# pwr.net
KiCad netlist of a schematic drawn in Altium Designer
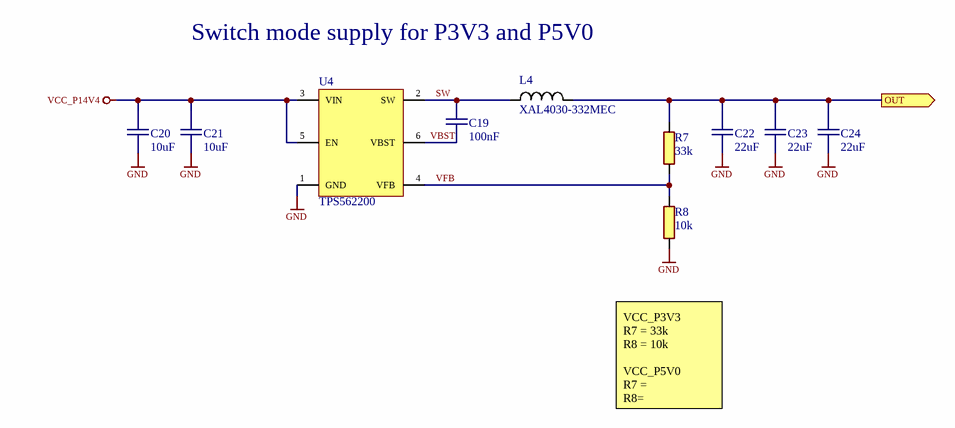
[diagram p0: pwr.SchDoc]

(export (version "E")
  (design (tool "Eeschema 10.0.6"))
  (components
    (comp (ref "C19")
      (value "100nF")
      (footprint "CAPC0603(1608)55_N")
      (description "X7R 50V 5%")
      (libsource (lib "OVLib_64") (part "CAP"))
    )
    (comp (ref "C20")
      (value "10uF")
      (footprint "CAPC1206(3216)170_N")
      (description "X5R 50V 10%")
      (libsource (lib "OVLib_64") (part "CAP"))
    )
    (comp (ref "C21")
      (value "10uF")
      (footprint "CAPC1206(3216)170_N")
      (description "X5R 50V 10%")
      (libsource (lib "OVLib_64") (part "CAP"))
    )
    (comp (ref "C22")
      (value "22uF")
      (footprint "CAPC1206(3216)170_N")
      (description "10V 10% Tantalum")
      (libsource (lib "OVLib_64") (part "CAP"))
    )
    (comp (ref "C23")
      (value "22uF")
      (footprint "CAPC1206(3216)170_N")
      (description "10V 10% Tantalum")
      (libsource (lib "OVLib_64") (part "CAP"))
    )
    (comp (ref "C24")
      (value "22uF")
      (footprint "CAPC1206(3216)170_N")
      (description "10V 10% Tantalum")
      (libsource (lib "OVLib_64") (part "CAP"))
    )
    (comp (ref "L4")
      (value "XAL4030-332MEC")
      (footprint "XAL4030")
      (description "3.3µH")
      (libsource (lib "OVLib_64") (part "IND_GENERIC"))
    )
    (comp (ref "R7")
      (value "33k")
      (footprint "RESC0603(1608)_N")
      (description "0.1W 1% Thick film resistor")
      (libsource (lib "OVLib_64") (part "Resistor2"))
    )
    (comp (ref "R8")
      (value "10k")
      (footprint "RESC0603(1608)_N")
      (description "0.1W 1% Thick film resistor")
      (libsource (lib "OVLib_64") (part "Resistor2"))
    )
    (comp (ref "U4")
      (value "TPS562200")
      (footprint "SOT95P280X145-6N")
      (libsource (lib "OVLib_64") (part "TPS562200"))
    )
  )
  (nets
    (net (code "1") (name "/OUT") (class "Default")
      (node (ref "C22") (pin "2") (pinfunction "2_2") (pintype "passive"))
      (node (ref "C23") (pin "2") (pinfunction "2_2") (pintype "passive"))
      (node (ref "C24") (pin "2") (pinfunction "2_2") (pintype "passive"))
      (node (ref "L4") (pin "2") (pinfunction "2_2") (pintype "passive"))
      (node (ref "R7") (pin "2") (pinfunction "2_2") (pintype "passive"))
    )
    (net (code "2") (name "/SW") (class "Default")
      (node (ref "C19") (pin "2") (pinfunction "2_2") (pintype "passive"))
      (node (ref "L4") (pin "1") (pinfunction "1_1") (pintype "passive"))
      (node (ref "U4") (pin "2") (pinfunction "SW_2") (pintype "passive"))
    )
    (net (code "3") (name "/VBST") (class "Default")
      (node (ref "C19") (pin "1") (pinfunction "1_1") (pintype "passive"))
      (node (ref "U4") (pin "6") (pinfunction "VBST_6") (pintype "passive"))
    )
    (net (code "4") (name "/VFB") (class "Default")
      (node (ref "R7") (pin "1") (pinfunction "1_1") (pintype "passive"))
      (node (ref "R8") (pin "2") (pinfunction "2_2") (pintype "passive"))
      (node (ref "U4") (pin "4") (pinfunction "VFB_4") (pintype "passive"))
    )
    (net (code "5") (name "GND") (class "Default")
      (node (ref "C20") (pin "1") (pinfunction "1_1") (pintype "passive"))
      (node (ref "C21") (pin "1") (pinfunction "1_1") (pintype "passive"))
      (node (ref "C22") (pin "1") (pinfunction "1_1") (pintype "passive"))
      (node (ref "C23") (pin "1") (pinfunction "1_1") (pintype "passive"))
      (node (ref "C24") (pin "1") (pinfunction "1_1") (pintype "passive"))
      (node (ref "R8") (pin "1") (pinfunction "1_1") (pintype "passive"))
      (node (ref "U4") (pin "1") (pinfunction "GND_1") (pintype "passive"))
    )
    (net (code "6") (name "VCC_P14V4") (class "Default")
      (node (ref "C20") (pin "2") (pinfunction "2_2") (pintype "passive"))
      (node (ref "C21") (pin "2") (pinfunction "2_2") (pintype "passive"))
      (node (ref "U4") (pin "3") (pinfunction "VIN_3") (pintype "passive"))
      (node (ref "U4") (pin "5") (pinfunction "EN_5") (pintype "passive"))
    )
  )
)
